# TopLevel.net
KiCad netlist of a schematic drawn in Altium Designer
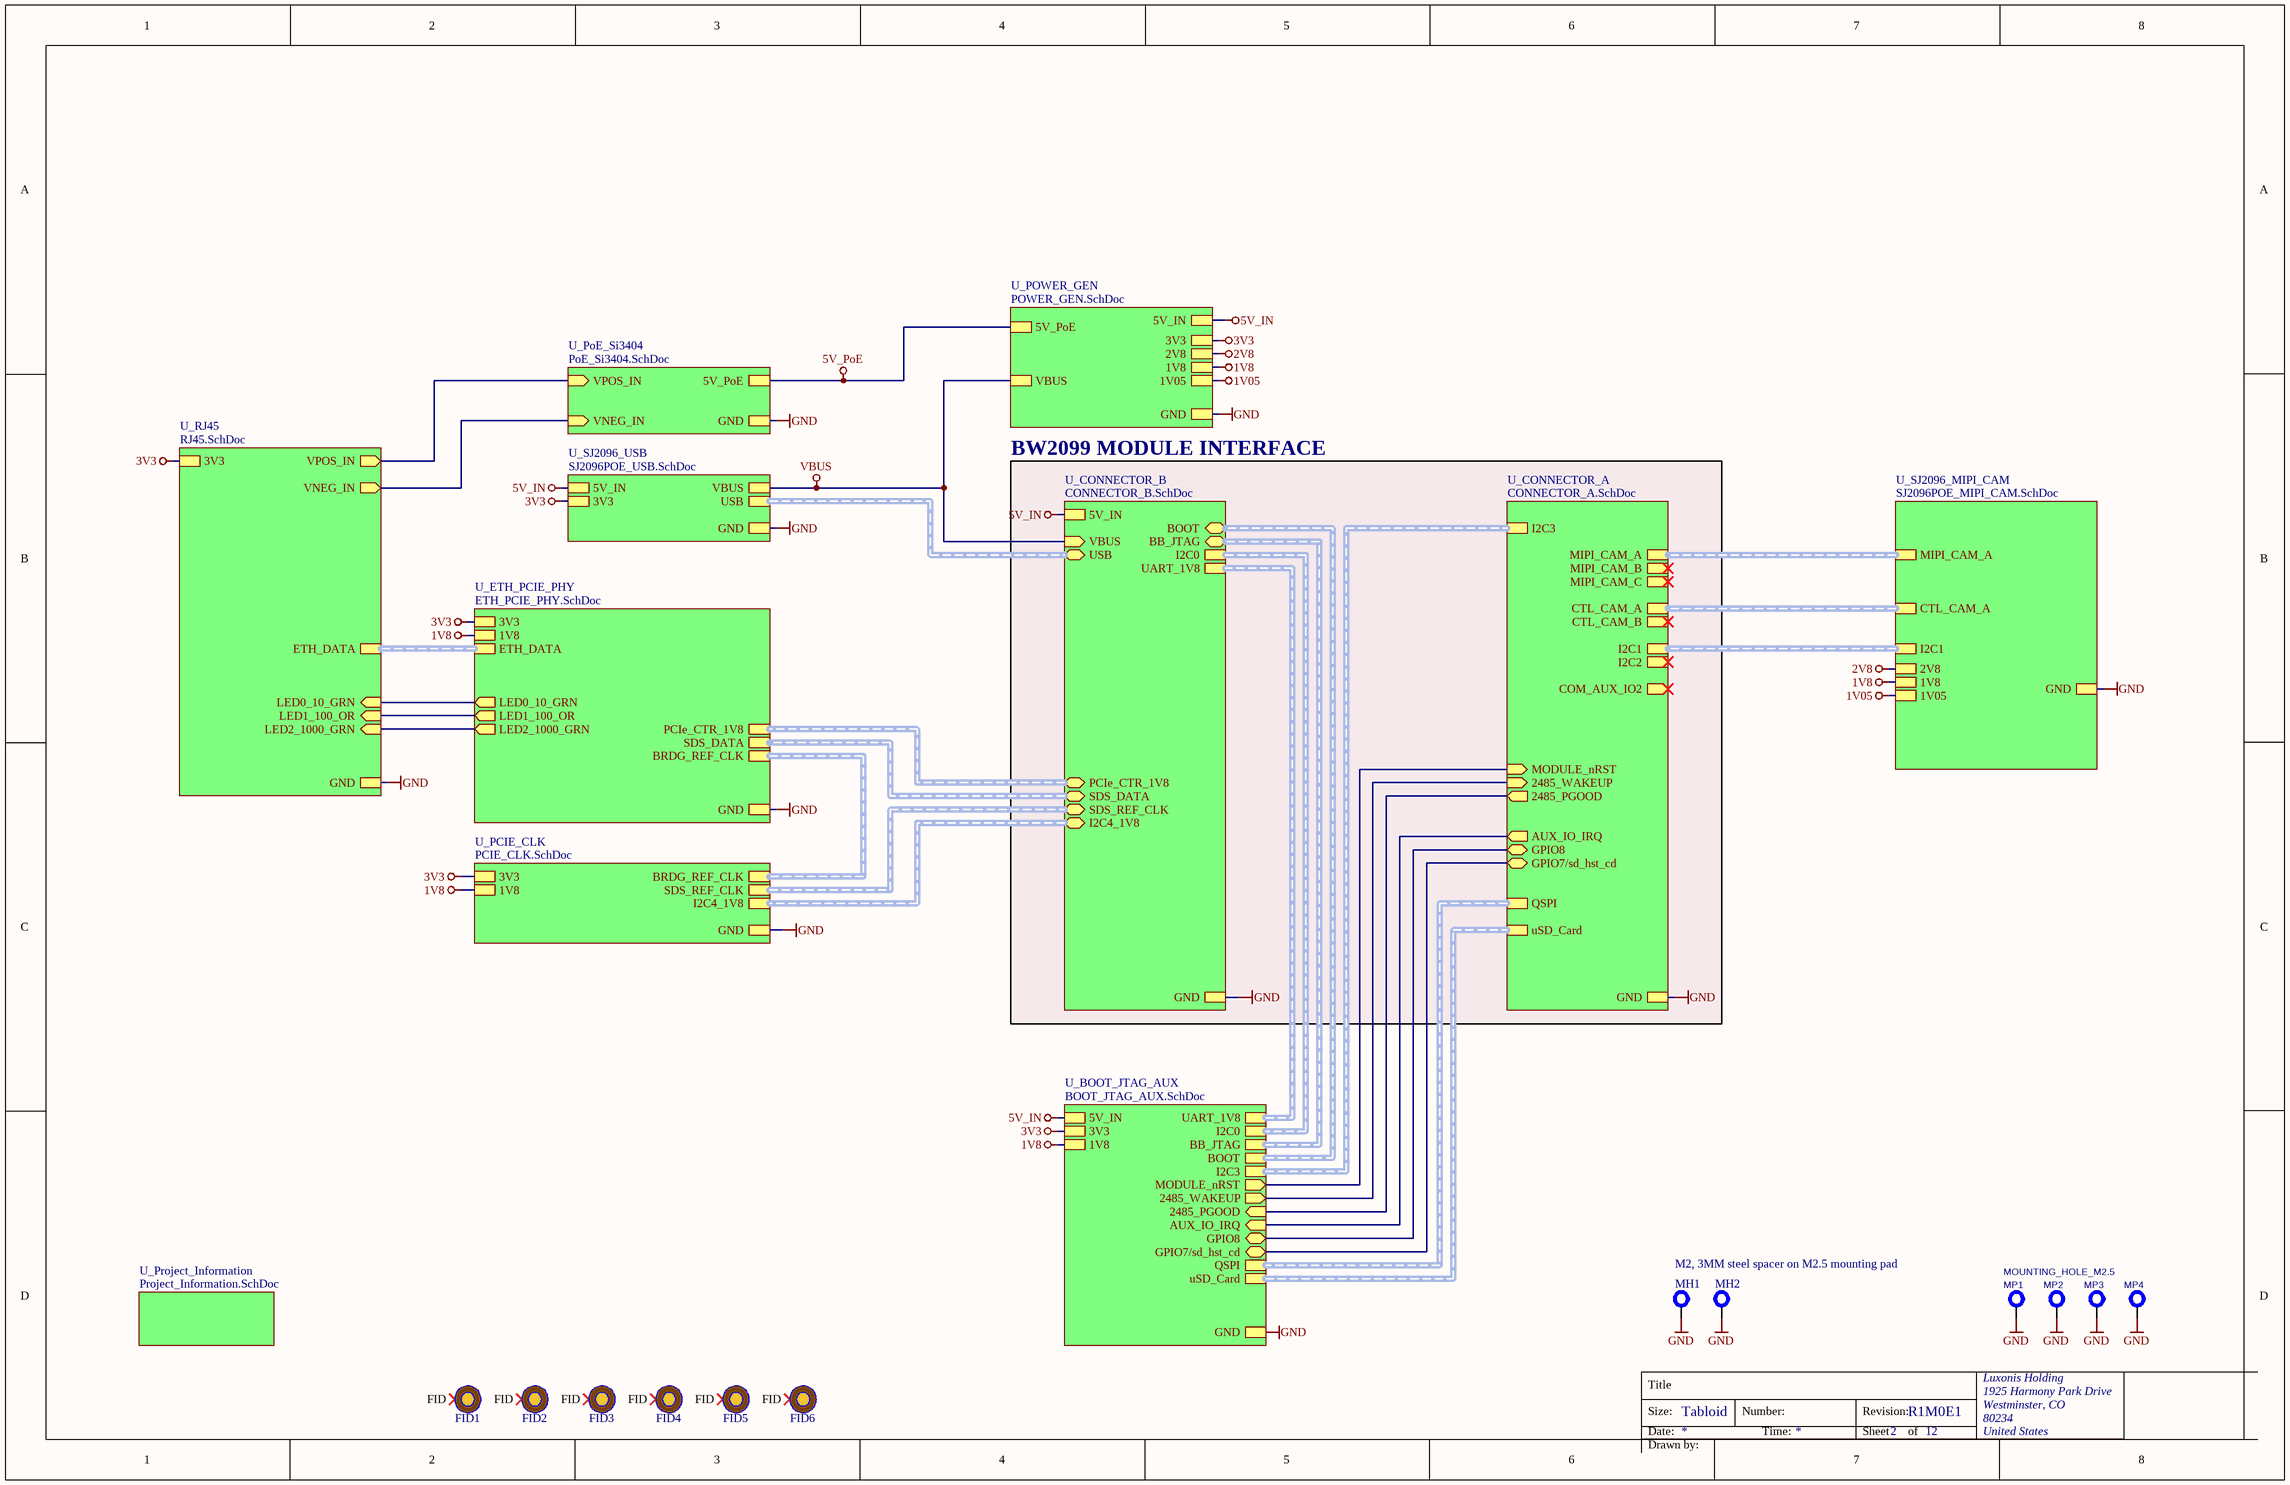
[diagram p0: TopLevel.SchDoc]

(export (version "E")
  (design (tool "Eeschema 10.0.6"))
  (components
    (comp (ref "FID1")
      (value "FIDUCIAL_ROUND_1MM")
      (footprint "LuxonisMaster:FIDUCIAL_ROUND_1MM")
      (description "Fiducial with various available footprints")
      (libsource (lib "LuxonisMaster") (part "FIDUCIAL"))
    )
    (comp (ref "FID2")
      (value "FIDUCIAL_ROUND_1MM")
      (footprint "LuxonisMaster:FIDUCIAL_ROUND_1MM")
      (description "Fiducial with various available footprints")
      (libsource (lib "LuxonisMaster") (part "FIDUCIAL"))
    )
    (comp (ref "FID3")
      (value "FIDUCIAL_ROUND_1MM")
      (footprint "LuxonisMaster:FIDUCIAL_ROUND_1MM")
      (description "Fiducial with various available footprints")
      (libsource (lib "LuxonisMaster") (part "FIDUCIAL"))
    )
    (comp (ref "FID4")
      (value "FIDUCIAL_ROUND_1MM")
      (footprint "LuxonisMaster:FIDUCIAL_ROUND_1MM")
      (description "Fiducial with various available footprints")
      (libsource (lib "LuxonisMaster") (part "FIDUCIAL"))
    )
    (comp (ref "FID5")
      (value "FIDUCIAL_ROUND_1MM")
      (footprint "LuxonisMaster:FIDUCIAL_ROUND_1MM")
      (description "Fiducial with various available footprints")
      (libsource (lib "LuxonisMaster") (part "FIDUCIAL"))
    )
    (comp (ref "FID6")
      (value "FIDUCIAL_ROUND_1MM")
      (footprint "LuxonisMaster:FIDUCIAL_ROUND_1MM")
      (description "Fiducial with various available footprints")
      (libsource (lib "LuxonisMaster") (part "FIDUCIAL"))
    )
    (comp (ref "MH1")
      (value "M2, 3MM steel spacer on M2.5 mounting pad")
      (footprint "LuxonisMaster:9774030243R")
      (description "MP ROUND STANDOFF M2X0.4 STEEL 3MM")
      (libsource (lib "LuxonisMaster") (part "9774030243R"))
    )
    (comp (ref "MH2")
      (value "M2, 3MM steel spacer on M2.5 mounting pad")
      (footprint "LuxonisMaster:9774030243R")
      (description "MP ROUND STANDOFF M2X0.4 STEEL 3MM")
      (libsource (lib "LuxonisMaster") (part "9774030243R"))
    )
    (comp (ref "MP1")
      (value "MOUNTING_HOLE_M2.5")
      (footprint "LuxonisMaster:MOUNTING_HOLE_M2.5")
      (description "=CurrentFootprint")
      (libsource (lib "LuxonisMaster") (part "MP_Mounting-Holes"))
    )
    (comp (ref "MP2")
      (value "MOUNTING_HOLE_M2.5")
      (footprint "LuxonisMaster:MOUNTING_HOLE_M2.5")
      (description "=CurrentFootprint")
      (libsource (lib "LuxonisMaster") (part "MP_Mounting-Holes"))
    )
    (comp (ref "MP3")
      (value "MOUNTING_HOLE_M2.5")
      (footprint "LuxonisMaster:MOUNTING_HOLE_M2.5")
      (description "=CurrentFootprint")
      (libsource (lib "LuxonisMaster") (part "MP_Mounting-Holes"))
    )
    (comp (ref "MP4")
      (value "MOUNTING_HOLE_M2.5")
      (footprint "LuxonisMaster:MOUNTING_HOLE_M2.5")
      (description "=CurrentFootprint")
      (libsource (lib "LuxonisMaster") (part "MP_Mounting-Holes"))
    )
  )
  (nets
    (net (code "40") (name "GND") (class "Default")
      (node (ref "MH1") (pin "1") (pintype "passive"))
      (node (ref "MH2") (pin "1") (pintype "passive"))
      (node (ref "MP1") (pin "1") (pintype "passive"))
      (node (ref "MP2") (pin "1") (pintype "passive"))
      (node (ref "MP3") (pin "1") (pintype "passive"))
      (node (ref "MP4") (pin "1") (pintype "passive"))
    )
    (net (code "42") (name "unconnected-(FID1-PadFID)") (class "Default")
      (node (ref "FID1") (pin "FID") (pinfunction "FID_FID") (pintype "input+no_connect"))
    )
    (net (code "43") (name "unconnected-(FID2-PadFID)") (class "Default")
      (node (ref "FID2") (pin "FID") (pinfunction "FID_FID") (pintype "input+no_connect"))
    )
    (net (code "44") (name "unconnected-(FID3-PadFID)") (class "Default")
      (node (ref "FID3") (pin "FID") (pinfunction "FID_FID") (pintype "input+no_connect"))
    )
    (net (code "45") (name "unconnected-(FID4-PadFID)") (class "Default")
      (node (ref "FID4") (pin "FID") (pinfunction "FID_FID") (pintype "input+no_connect"))
    )
    (net (code "46") (name "unconnected-(FID5-PadFID)") (class "Default")
      (node (ref "FID5") (pin "FID") (pinfunction "FID_FID") (pintype "input+no_connect"))
    )
    (net (code "47") (name "unconnected-(FID6-PadFID)") (class "Default")
      (node (ref "FID6") (pin "FID") (pinfunction "FID_FID") (pintype "input+no_connect"))
    )
  )
)
